# Sheet1.net
KiCad netlist of a schematic drawn in Altium Designer
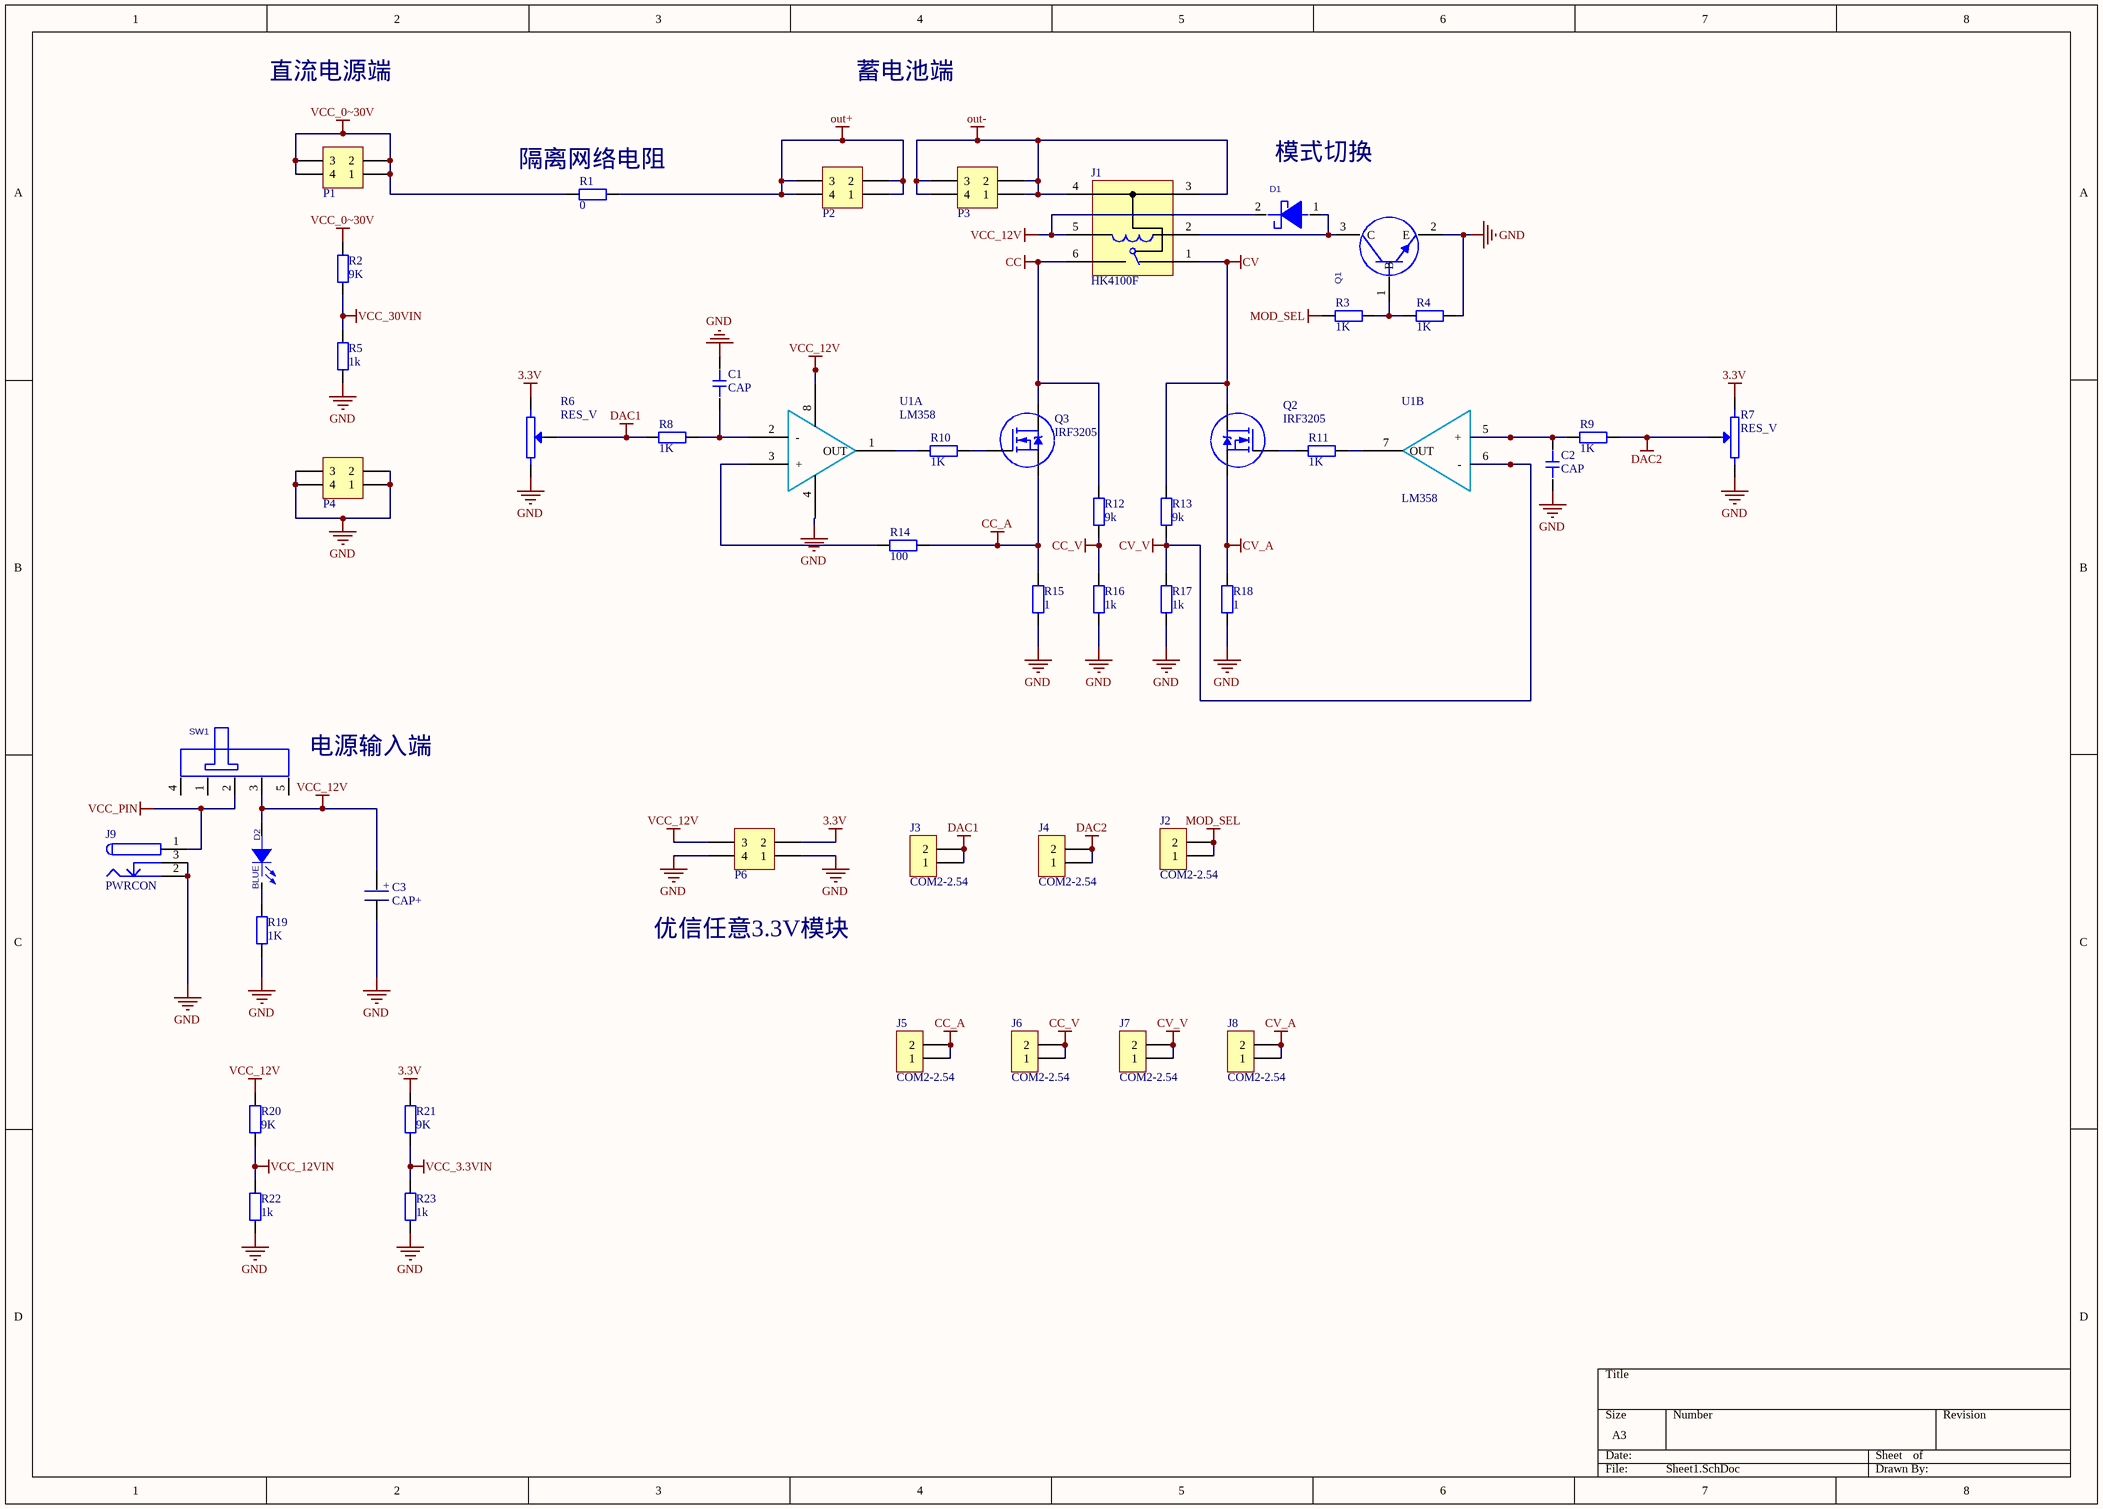
[diagram p0: Sheet1.SchDoc]

(export (version "E")
  (design (tool "Eeschema 10.0.6"))
  (components
    (comp (ref "C1") (value "CAP") (footprint "C_0805") (libsource (lib "XJDYJB-v1.07") (part "CAP")))
    (comp (ref "C2") (value "CAP") (footprint "C_0805") (libsource (lib "XJDYJB-v1.07") (part "CAP")))
    (comp (ref "C3") (value "CAP+") (footprint "CAP_2") (libsource (lib "XJDYJB-v1.07") (part "CAP+")))
    (comp (ref "D1")
      (value "SMAJ5.0CA")
      (footprint "DO-214-A")
      (description "SMAJ5.0CA-E3/61 400W 5V")
      (libsource (lib "XJDYJB-v1.07") (part "SMAJ5.0CA"))
    )
    (comp (ref "D2")
      (value "BLUE")
      (footprint "LED_0603")
      (fields (field (name "Comment") "LED"))
      (libsource (lib "XJDYJB-v1.07") (part "LED"))
    )
    (comp (ref "J1")
      (value "HK4100F")
      (footprint "RELAY-HK4100F")
      (description "单刀双掷继电器")
      (libsource (lib "Fszhang") (part "HK4100F"))
    )
    (comp (ref "J2")
      (value "COM2-2.54")
      (footprint "HDR2X1-2.54")
      (libsource (lib "XJDYJB-v1.07") (part "COM2-2.54"))
    )
    (comp (ref "J3")
      (value "COM2-2.54")
      (footprint "HDR2X1-2.54")
      (libsource (lib "XJDYJB-v1.07") (part "COM2-2.54"))
    )
    (comp (ref "J4")
      (value "COM2-2.54")
      (footprint "HDR2X1-2.54")
      (libsource (lib "XJDYJB-v1.07") (part "COM2-2.54"))
    )
    (comp (ref "J5")
      (value "COM2-2.54")
      (footprint "HDR2X1-2.54")
      (libsource (lib "XJDYJB-v1.07") (part "COM2-2.54"))
    )
    (comp (ref "J6")
      (value "COM2-2.54")
      (footprint "HDR2X1-2.54")
      (libsource (lib "XJDYJB-v1.07") (part "COM2-2.54"))
    )
    (comp (ref "J7")
      (value "COM2-2.54")
      (footprint "HDR2X1-2.54")
      (libsource (lib "XJDYJB-v1.07") (part "COM2-2.54"))
    )
    (comp (ref "J8")
      (value "COM2-2.54")
      (footprint "HDR2X1-2.54")
      (libsource (lib "XJDYJB-v1.07") (part "COM2-2.54"))
    )
    (comp (ref "J9")
      (value "PWRCON")
      (footprint "DC-005")
      (description "直流电源端子")
      (fields (field (name "PUBLISHER") "Altium Limited"))
      (libsource (lib "Fszhang") (part "PWRCON"))
    )
    (comp (ref "P1")
      (value "Header 2X2A")
      (footprint "HDR2X2-2.54")
      (description "接插件")
      (fields (field (name "PUBLISHER") "Altium Limited"))
      (libsource (lib "Fszhang") (part "Header 2X2A"))
    )
    (comp (ref "P2")
      (value "Header 2X2A")
      (footprint "HDR2X2-2.54")
      (description "接插件")
      (fields (field (name "PUBLISHER") "Altium Limited"))
      (libsource (lib "Fszhang") (part "Header 2X2A"))
    )
    (comp (ref "P3")
      (value "Header 2X2A")
      (footprint "HDR2X2-2.54")
      (description "接插件")
      (fields (field (name "PUBLISHER") "Altium Limited"))
      (libsource (lib "Fszhang") (part "Header 2X2A"))
    )
    (comp (ref "P4")
      (value "Header 2X2A")
      (footprint "HDR2X2-2.54")
      (description "接插件")
      (fields (field (name "PUBLISHER") "Altium Limited"))
      (libsource (lib "Fszhang") (part "Header 2X2A"))
    )
    (comp (ref "P6")
      (value "Header 2X2A")
      (footprint "HDR2X2-2.54")
      (description "接插件")
      (fields (field (name "PUBLISHER") "Altium Limited"))
      (libsource (lib "Fszhang") (part "Header 2X2A"))
    )
    (comp (ref "Q1")
      (value "8050")
      (footprint "SOT-23")
      (description "NPN")
      (libsource (lib "XJDYJB-v1.07") (part "8050"))
    )
    (comp (ref "Q2") (value "IRF3205") (footprint "TO-220L") (libsource (lib "DP1006元件库") (part "IRF3205")))
    (comp (ref "Q3") (value "IRF3205") (footprint "TO-220L") (libsource (lib "") (part "IRF3205_1")))
    (comp (ref "R1")
      (value "0")
      (footprint "1210")
      (description "贴片电阻")
      (fields (field (name "Comment") "Res1") (field (name "PUBLISHER") "Altium Limited"))
      (libsource (lib "Fszhang") (part "Res1"))
    )
    (comp (ref "R2")
      (value "9K")
      (footprint "0603-1")
      (description "贴片电阻")
      (fields (field (name "Comment") "Res1") (field (name "PUBLISHER") "Altium Limited"))
      (libsource (lib "") (part "Res1_2"))
    )
    (comp (ref "R3")
      (value "1K")
      (footprint "0603-1")
      (description "贴片电阻")
      (fields (field (name "Comment") "Res1") (field (name "PUBLISHER") "Altium Limited"))
      (libsource (lib "") (part "Res1_1"))
    )
    (comp (ref "R4")
      (value "1K")
      (footprint "0603-1")
      (description "贴片电阻")
      (fields (field (name "Comment") "Res1") (field (name "PUBLISHER") "Altium Limited"))
      (libsource (lib "Fszhang") (part "Res1"))
    )
    (comp (ref "R5")
      (value "1k")
      (footprint "0603-1")
      (description "贴片电阻")
      (fields (field (name "Comment") "Res1") (field (name "PUBLISHER") "Altium Limited"))
      (libsource (lib "") (part "Res1_2"))
    )
    (comp (ref "R6") (value "RES_V") (footprint "RES_V4") (libsource (lib "XJDYJB-v1.07") (part "RES_V")))
    (comp (ref "R7") (value "RES_V") (footprint "RES_V4") (libsource (lib "XJDYJB-v1.07") (part "RES_V")))
    (comp (ref "R8")
      (value "1K")
      (footprint "0603-1")
      (description "贴片电阻")
      (fields (field (name "Comment") "Res1") (field (name "PUBLISHER") "Altium Limited"))
      (libsource (lib "") (part "Res1_1"))
    )
    (comp (ref "R9")
      (value "1K")
      (footprint "0603-1")
      (description "贴片电阻")
      (fields (field (name "Comment") "Res1") (field (name "PUBLISHER") "Altium Limited"))
      (libsource (lib "") (part "Res1_1"))
    )
    (comp (ref "R10")
      (value "1K")
      (footprint "0603-1")
      (description "贴片电阻")
      (fields (field (name "Comment") "Res1") (field (name "PUBLISHER") "Altium Limited"))
      (libsource (lib "") (part "Res1_1"))
    )
    (comp (ref "R11")
      (value "1K")
      (footprint "0603-1")
      (description "贴片电阻")
      (fields (field (name "Comment") "Res1") (field (name "PUBLISHER") "Altium Limited"))
      (libsource (lib "") (part "Res1_1"))
    )
    (comp (ref "R12")
      (value "9k")
      (footprint "0603-1")
      (description "贴片电阻")
      (fields (field (name "Comment") "Res1") (field (name "PUBLISHER") "Altium Limited"))
      (libsource (lib "") (part "Res1_2"))
    )
    (comp (ref "R13")
      (value "9k")
      (footprint "0603-1")
      (description "贴片电阻")
      (fields (field (name "Comment") "Res1") (field (name "PUBLISHER") "Altium Limited"))
      (libsource (lib "") (part "Res1_1"))
    )
    (comp (ref "R14")
      (value "100")
      (footprint "1210")
      (description "贴片电阻")
      (fields (field (name "Comment") "Res1") (field (name "PUBLISHER") "Altium Limited"))
      (libsource (lib "Fszhang") (part "Res1"))
    )
    (comp (ref "R15")
      (value "1")
      (footprint "1210")
      (description "贴片电阻")
      (fields (field (name "Comment") "Res1") (field (name "PUBLISHER") "Altium Limited"))
      (libsource (lib "") (part "Res1_2"))
    )
    (comp (ref "R16")
      (value "1k")
      (footprint "0603-1")
      (description "贴片电阻")
      (fields (field (name "Comment") "Res1") (field (name "PUBLISHER") "Altium Limited"))
      (libsource (lib "") (part "Res1_2"))
    )
    (comp (ref "R17")
      (value "1k")
      (footprint "0603-1")
      (description "贴片电阻")
      (fields (field (name "Comment") "Res1") (field (name "PUBLISHER") "Altium Limited"))
      (libsource (lib "") (part "Res1_1"))
    )
    (comp (ref "R18")
      (value "1")
      (footprint "1210")
      (description "贴片电阻")
      (fields (field (name "Comment") "Res1") (field (name "PUBLISHER") "Altium Limited"))
      (libsource (lib "") (part "Res1_1"))
    )
    (comp (ref "R19")
      (value "1K")
      (footprint "0603-1")
      (description "贴片电阻")
      (fields (field (name "Comment") "Res1") (field (name "PUBLISHER") "Altium Limited"))
      (libsource (lib "") (part "Res1_2"))
    )
    (comp (ref "R20")
      (value "9K")
      (footprint "0603-1")
      (description "贴片电阻")
      (fields (field (name "Comment") "Res1") (field (name "PUBLISHER") "Altium Limited"))
      (libsource (lib "") (part "Res1_2"))
    )
    (comp (ref "R21")
      (value "9K")
      (footprint "0603-1")
      (description "贴片电阻")
      (fields (field (name "Comment") "Res1") (field (name "PUBLISHER") "Altium Limited"))
      (libsource (lib "") (part "Res1_2"))
    )
    (comp (ref "R22")
      (value "1k")
      (footprint "0603-1")
      (description "贴片电阻")
      (fields (field (name "Comment") "Res1") (field (name "PUBLISHER") "Altium Limited"))
      (libsource (lib "") (part "Res1_2"))
    )
    (comp (ref "R23")
      (value "1k")
      (footprint "0603-1")
      (description "贴片电阻")
      (fields (field (name "Comment") "Res1") (field (name "PUBLISHER") "Altium Limited"))
      (libsource (lib "") (part "Res1_2"))
    )
    (comp (ref "SW1")
      (value "SW-POWER")
      (footprint "SW13_6")
      (description "SW-5")
      (libsource (lib "XJDYJB-v1.07") (part "SW-POWER"))
    )
    (comp (ref "U1") (value "LM358") (footprint "SOP8") (libsource (lib "XJDYJB-v1.24") (part "LM358")))
  )
  (nets
    (net (code "1") (name "3.3V") (class "Default")
      (node (ref "P6") (pin "2") (pinfunction "2_2") (pintype "passive"))
      (node (ref "R21") (pin "2") (pinfunction "2_2") (pintype "passive"))
      (node (ref "R6") (pin "4") (pinfunction "4_4") (pintype "passive"))
      (node (ref "R7") (pin "4") (pinfunction "4_4") (pintype "passive"))
    )
    (net (code "2") (name "CC") (class "Default")
      (node (ref "J1") (pin "6") (pinfunction "6_6") (pintype "passive"))
      (node (ref "Q3") (pin "2") (pinfunction "D_2") (pintype "passive"))
      (node (ref "R12") (pin "2") (pinfunction "2_2") (pintype "passive"))
    )
    (net (code "3") (name "CC_A") (class "Default")
      (node (ref "J5") (pin "1") (pinfunction "1_1") (pintype "passive"))
      (node (ref "J5") (pin "2") (pinfunction "2_2") (pintype "passive"))
      (node (ref "Q3") (pin "3") (pinfunction "S_3") (pintype "passive"))
      (node (ref "R14") (pin "1") (pinfunction "1_1") (pintype "passive"))
      (node (ref "R15") (pin "2") (pinfunction "2_2") (pintype "passive"))
    )
    (net (code "4") (name "CC_V") (class "Default")
      (node (ref "J6") (pin "1") (pinfunction "1_1") (pintype "passive"))
      (node (ref "J6") (pin "2") (pinfunction "2_2") (pintype "passive"))
      (node (ref "R12") (pin "1") (pinfunction "1_1") (pintype "passive"))
      (node (ref "R16") (pin "2") (pinfunction "2_2") (pintype "passive"))
    )
    (net (code "5") (name "CV") (class "Default")
      (node (ref "J1") (pin "1") (pinfunction "1_1") (pintype "passive"))
      (node (ref "Q2") (pin "2") (pinfunction "D_2") (pintype "passive"))
      (node (ref "R13") (pin "2") (pinfunction "2_2") (pintype "passive"))
    )
    (net (code "6") (name "CV_A") (class "Default")
      (node (ref "J8") (pin "1") (pinfunction "1_1") (pintype "passive"))
      (node (ref "J8") (pin "2") (pinfunction "2_2") (pintype "passive"))
      (node (ref "Q2") (pin "3") (pinfunction "S_3") (pintype "passive"))
      (node (ref "R18") (pin "2") (pinfunction "2_2") (pintype "passive"))
    )
    (net (code "7") (name "CV_V") (class "Default")
      (node (ref "J7") (pin "1") (pinfunction "1_1") (pintype "passive"))
      (node (ref "J7") (pin "2") (pinfunction "2_2") (pintype "passive"))
      (node (ref "R13") (pin "1") (pinfunction "1_1") (pintype "passive"))
      (node (ref "R17") (pin "2") (pinfunction "2_2") (pintype "passive"))
      (node (ref "U1") (pin "6") (pinfunction "-_6") (pintype "passive"))
    )
    (net (code "8") (name "DAC1") (class "Default")
      (node (ref "J3") (pin "1") (pinfunction "1_1") (pintype "passive"))
      (node (ref "J3") (pin "2") (pinfunction "2_2") (pintype "passive"))
      (node (ref "R6") (pin "5") (pinfunction "W_5") (pintype "passive"))
      (node (ref "R8") (pin "1") (pinfunction "1_1") (pintype "passive"))
    )
    (net (code "9") (name "DAC2") (class "Default")
      (node (ref "J4") (pin "1") (pinfunction "1_1") (pintype "passive"))
      (node (ref "J4") (pin "2") (pinfunction "2_2") (pintype "passive"))
      (node (ref "R7") (pin "5") (pinfunction "W_5") (pintype "passive"))
      (node (ref "R9") (pin "2") (pinfunction "2_2") (pintype "passive"))
    )
    (net (code "10") (name "GND") (class "Default")
      (node (ref "C1") (pin "2") (pinfunction "2_2") (pintype "passive"))
      (node (ref "C2") (pin "2") (pinfunction "2_2") (pintype "passive"))
      (node (ref "C3") (pin "2") (pinfunction "2_2") (pintype "passive"))
      (node (ref "J9") (pin "2") (pinfunction "2_2") (pintype "power_in"))
      (node (ref "J9") (pin "3") (pinfunction "3_3") (pintype "power_in"))
      (node (ref "P4") (pin "1") (pinfunction "1_1") (pintype "passive"))
      (node (ref "P4") (pin "2") (pinfunction "2_2") (pintype "passive"))
      (node (ref "P4") (pin "3") (pinfunction "3_3") (pintype "passive"))
      (node (ref "P4") (pin "4") (pinfunction "4_4") (pintype "passive"))
      (node (ref "P6") (pin "1") (pinfunction "1_1") (pintype "passive"))
      (node (ref "P6") (pin "4") (pinfunction "4_4") (pintype "passive"))
      (node (ref "Q1") (pin "2") (pinfunction "E_2") (pintype "passive"))
      (node (ref "R15") (pin "1") (pinfunction "1_1") (pintype "passive"))
      (node (ref "R16") (pin "1") (pinfunction "1_1") (pintype "passive"))
      (node (ref "R17") (pin "1") (pinfunction "1_1") (pintype "passive"))
      (node (ref "R18") (pin "1") (pinfunction "1_1") (pintype "passive"))
      (node (ref "R19") (pin "1") (pinfunction "1_1") (pintype "passive"))
      (node (ref "R22") (pin "1") (pinfunction "1_1") (pintype "passive"))
      (node (ref "R23") (pin "1") (pinfunction "1_1") (pintype "passive"))
      (node (ref "R4") (pin "1") (pinfunction "1_1") (pintype "passive"))
      (node (ref "R5") (pin "1") (pinfunction "1_1") (pintype "passive"))
      (node (ref "R6") (pin "6") (pinfunction "6_6") (pintype "passive"))
      (node (ref "R7") (pin "6") (pinfunction "6_6") (pintype "passive"))
      (node (ref "U1") (pin "4") (pinfunction "-VCC_4") (pintype "passive"))
    )
    (net (code "11") (name "MOD_SEL") (class "Default")
      (node (ref "J2") (pin "1") (pinfunction "1_1") (pintype "passive"))
      (node (ref "J2") (pin "2") (pinfunction "2_2") (pintype "passive"))
      (node (ref "R3") (pin "1") (pinfunction "1_1") (pintype "passive"))
    )
    (net (code "12") (name "Net-(D1-+)") (class "Default")
      (node (ref "D1") (pin "1") (pinfunction "+_1") (pintype "passive"))
      (node (ref "J1") (pin "2") (pinfunction "2_2") (pintype "passive"))
      (node (ref "Q1") (pin "3") (pinfunction "C_3") (pintype "passive"))
    )
    (net (code "13") (name "Net-(D2-CATHODE)") (class "Default")
      (node (ref "D2") (pin "2") (pinfunction "CATHODE_2") (pintype "passive"))
      (node (ref "R19") (pin "2") (pinfunction "2_2") (pintype "passive"))
    )
    (net (code "14") (name "Net-(Q1-B)") (class "Default")
      (node (ref "Q1") (pin "1") (pinfunction "B_1") (pintype "passive"))
      (node (ref "R3") (pin "2") (pinfunction "2_2") (pintype "passive"))
      (node (ref "R4") (pin "2") (pinfunction "2_2") (pintype "passive"))
    )
    (net (code "15") (name "Net-(Q2-G)") (class "Default")
      (node (ref "Q2") (pin "1") (pinfunction "G_1") (pintype "passive"))
      (node (ref "R11") (pin "1") (pinfunction "1_1") (pintype "passive"))
    )
    (net (code "16") (name "Net-(Q3-G)") (class "Default")
      (node (ref "Q3") (pin "1") (pinfunction "G_1") (pintype "passive"))
      (node (ref "R10") (pin "2") (pinfunction "2_2") (pintype "passive"))
    )
    (net (code "17") (name "Net-(U1A-+)") (class "Default")
      (node (ref "R14") (pin "2") (pinfunction "2_2") (pintype "passive"))
      (node (ref "U1") (pin "3") (pinfunction "+_3") (pintype "passive"))
    )
    (net (code "18") (name "Net-(U1A--)") (class "Default")
      (node (ref "C1") (pin "1") (pinfunction "1_1") (pintype "passive"))
      (node (ref "R8") (pin "2") (pinfunction "2_2") (pintype "passive"))
      (node (ref "U1") (pin "2") (pinfunction "-_2") (pintype "passive"))
    )
    (net (code "19") (name "Net-(U1A-OUT)") (class "Default")
      (node (ref "R10") (pin "1") (pinfunction "1_1") (pintype "passive"))
      (node (ref "U1") (pin "1") (pinfunction "OUT_1") (pintype "passive"))
    )
    (net (code "20") (name "Net-(U1B-+)") (class "Default")
      (node (ref "C2") (pin "1") (pinfunction "1_1") (pintype "passive"))
      (node (ref "R9") (pin "1") (pinfunction "1_1") (pintype "passive"))
      (node (ref "U1") (pin "5") (pinfunction "+_5") (pintype "passive"))
    )
    (net (code "21") (name "Net-(U1B-OUT)") (class "Default")
      (node (ref "R11") (pin "2") (pinfunction "2_2") (pintype "passive"))
      (node (ref "U1") (pin "7") (pinfunction "OUT_7") (pintype "passive"))
    )
    (net (code "22") (name "VCC_0~30V") (class "Default")
      (node (ref "P1") (pin "1") (pinfunction "1_1") (pintype "passive"))
      (node (ref "P1") (pin "2") (pinfunction "2_2") (pintype "passive"))
      (node (ref "P1") (pin "3") (pinfunction "3_3") (pintype "passive"))
      (node (ref "P1") (pin "4") (pinfunction "4_4") (pintype "passive"))
      (node (ref "R1") (pin "2") (pinfunction "2_2") (pintype "passive"))
      (node (ref "R2") (pin "2") (pinfunction "2_2") (pintype "passive"))
    )
    (net (code "23") (name "VCC_3.3VIN") (class "Default")
      (node (ref "R21") (pin "1") (pinfunction "1_1") (pintype "passive"))
      (node (ref "R23") (pin "2") (pinfunction "2_2") (pintype "passive"))
    )
    (net (code "24") (name "VCC_12V") (class "Default")
      (node (ref "C3") (pin "1") (pinfunction "1_1") (pintype "passive"))
      (node (ref "D1") (pin "2") (pinfunction "-_2") (pintype "passive"))
      (node (ref "D2") (pin "1") (pinfunction "ANODE_1") (pintype "passive"))
      (node (ref "J1") (pin "5") (pinfunction "5_5") (pintype "passive"))
      (node (ref "P6") (pin "3") (pinfunction "3_3") (pintype "passive"))
      (node (ref "R20") (pin "2") (pinfunction "2_2") (pintype "passive"))
      (node (ref "SW1") (pin "3") (pinfunction "3_3") (pintype "passive"))
      (node (ref "U1") (pin "8") (pinfunction "VCC_8") (pintype "passive"))
    )
    (net (code "25") (name "VCC_12VIN") (class "Default")
      (node (ref "R20") (pin "1") (pinfunction "1_1") (pintype "passive"))
      (node (ref "R22") (pin "2") (pinfunction "2_2") (pintype "passive"))
    )
    (net (code "26") (name "VCC_30VIN") (class "Default")
      (node (ref "R2") (pin "1") (pinfunction "1_1") (pintype "passive"))
      (node (ref "R5") (pin "2") (pinfunction "2_2") (pintype "passive"))
    )
    (net (code "27") (name "VCC_PIN") (class "Default")
      (node (ref "J9") (pin "1") (pinfunction "1_1") (pintype "power_in"))
      (node (ref "SW1") (pin "2") (pinfunction "2_2") (pintype "passive"))
    )
    (net (code "28") (name "out+") (class "Default")
      (node (ref "P2") (pin "1") (pinfunction "1_1") (pintype "passive"))
      (node (ref "P2") (pin "2") (pinfunction "2_2") (pintype "passive"))
      (node (ref "P2") (pin "3") (pinfunction "3_3") (pintype "passive"))
      (node (ref "P2") (pin "4") (pinfunction "4_4") (pintype "passive"))
      (node (ref "R1") (pin "1") (pinfunction "1_1") (pintype "passive"))
    )
    (net (code "29") (name "out-") (class "Default")
      (node (ref "J1") (pin "3") (pinfunction "3_3") (pintype "passive"))
      (node (ref "J1") (pin "4") (pinfunction "4_4") (pintype "passive"))
      (node (ref "P3") (pin "1") (pinfunction "1_1") (pintype "passive"))
      (node (ref "P3") (pin "2") (pinfunction "2_2") (pintype "passive"))
      (node (ref "P3") (pin "3") (pinfunction "3_3") (pintype "passive"))
      (node (ref "P3") (pin "4") (pinfunction "4_4") (pintype "passive"))
    )
    (net (code "30") (name "unconnected-(SW1-Pad1)") (class "Default")
      (node (ref "SW1") (pin "1") (pinfunction "1_1") (pintype "passive"))
    )
    (net (code "31") (name "unconnected-(SW1-Pad4)") (class "Default")
      (node (ref "SW1") (pin "4") (pinfunction "4_4") (pintype "passive"))
    )
    (net (code "32") (name "unconnected-(SW1-Pad5)") (class "Default")
      (node (ref "SW1") (pin "5") (pinfunction "5_5") (pintype "passive"))
    )
  )
)
